# RGBM-05.net
KiCad netlist of a schematic drawn in Altium Designer
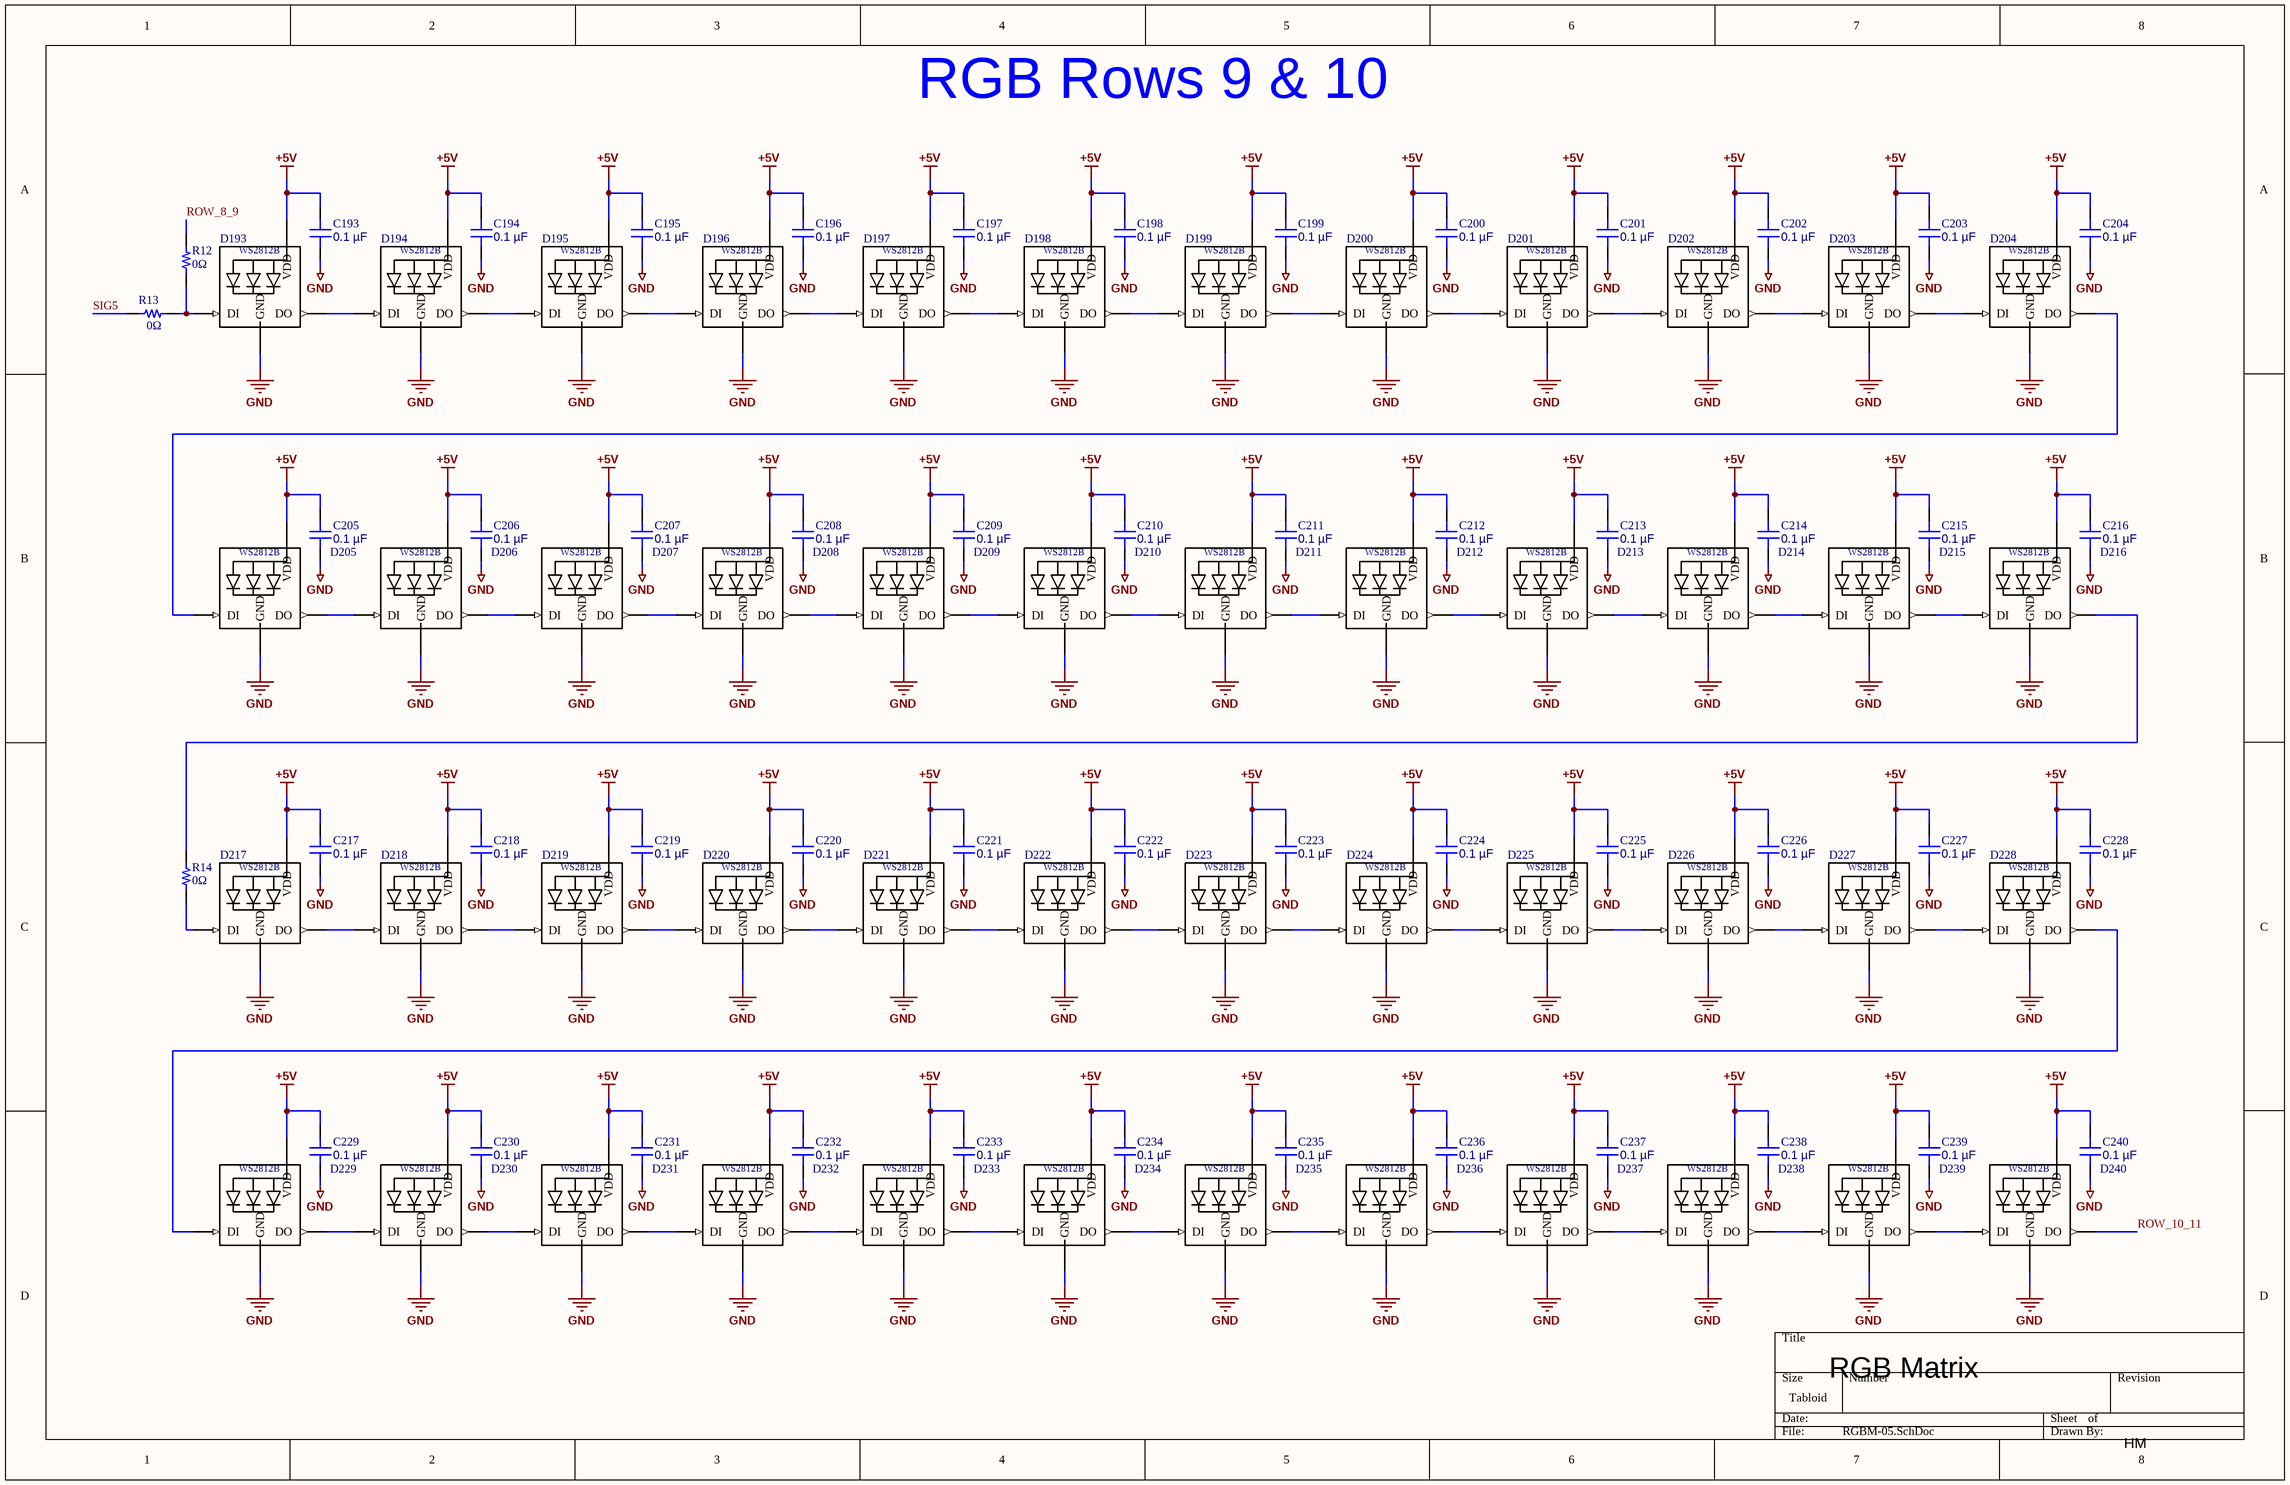
[diagram p0: RGBM-05.SchDoc]

(export (version "E")
  (design (tool "Eeschema 10.0.6"))
  (components
    (comp (ref "C193")
      (value "0.1 µF")
      (footprint "CAP 0603_1608")
      (description "CAP CER 0.1UF 50V X7R 0603")
      (fields
        (field (name "PART NUMBER") "C0603C104K5RAC7411")
        (field (name "CAPACITANCE") "0.1 µF")
        (field (name "MANUFACTURER") "KEMET")
      )
      (libsource (lib "Celestial Altium Library - altium_library") (part "Capacitor"))
    )
    (comp (ref "C194")
      (value "0.1 µF")
      (footprint "CAP 0603_1608")
      (description "CAP CER 0.1UF 50V X7R 0603")
      (fields
        (field (name "PART NUMBER") "C0603C104K5RAC7411")
        (field (name "CAPACITANCE") "0.1 µF")
        (field (name "MANUFACTURER") "KEMET")
      )
      (libsource (lib "Celestial Altium Library - altium_library") (part "Capacitor"))
    )
    (comp (ref "C195")
      (value "0.1 µF")
      (footprint "CAP 0603_1608")
      (description "CAP CER 0.1UF 50V X7R 0603")
      (fields
        (field (name "PART NUMBER") "C0603C104K5RAC7411")
        (field (name "CAPACITANCE") "0.1 µF")
        (field (name "MANUFACTURER") "KEMET")
      )
      (libsource (lib "Celestial Altium Library - altium_library") (part "Capacitor"))
    )
    (comp (ref "C196")
      (value "0.1 µF")
      (footprint "CAP 0603_1608")
      (description "CAP CER 0.1UF 50V X7R 0603")
      (fields
        (field (name "PART NUMBER") "C0603C104K5RAC7411")
        (field (name "CAPACITANCE") "0.1 µF")
        (field (name "MANUFACTURER") "KEMET")
      )
      (libsource (lib "Celestial Altium Library - altium_library") (part "Capacitor"))
    )
    (comp (ref "C197")
      (value "0.1 µF")
      (footprint "CAP 0603_1608")
      (description "CAP CER 0.1UF 50V X7R 0603")
      (fields
        (field (name "PART NUMBER") "C0603C104K5RAC7411")
        (field (name "CAPACITANCE") "0.1 µF")
        (field (name "MANUFACTURER") "KEMET")
      )
      (libsource (lib "Celestial Altium Library - altium_library") (part "Capacitor"))
    )
    (comp (ref "C198")
      (value "0.1 µF")
      (footprint "CAP 0603_1608")
      (description "CAP CER 0.1UF 50V X7R 0603")
      (fields
        (field (name "PART NUMBER") "C0603C104K5RAC7411")
        (field (name "CAPACITANCE") "0.1 µF")
        (field (name "MANUFACTURER") "KEMET")
      )
      (libsource (lib "Celestial Altium Library - altium_library") (part "Capacitor"))
    )
    (comp (ref "C199")
      (value "0.1 µF")
      (footprint "CAP 0603_1608")
      (description "CAP CER 0.1UF 50V X7R 0603")
      (fields
        (field (name "PART NUMBER") "C0603C104K5RAC7411")
        (field (name "CAPACITANCE") "0.1 µF")
        (field (name "MANUFACTURER") "KEMET")
      )
      (libsource (lib "Celestial Altium Library - altium_library") (part "Capacitor"))
    )
    (comp (ref "C200")
      (value "0.1 µF")
      (footprint "CAP 0603_1608")
      (description "CAP CER 0.1UF 50V X7R 0603")
      (fields
        (field (name "PART NUMBER") "C0603C104K5RAC7411")
        (field (name "CAPACITANCE") "0.1 µF")
        (field (name "MANUFACTURER") "KEMET")
      )
      (libsource (lib "Celestial Altium Library - altium_library") (part "Capacitor"))
    )
    (comp (ref "C201")
      (value "0.1 µF")
      (footprint "CAP 0603_1608")
      (description "CAP CER 0.1UF 50V X7R 0603")
      (fields
        (field (name "PART NUMBER") "C0603C104K5RAC7411")
        (field (name "CAPACITANCE") "0.1 µF")
        (field (name "MANUFACTURER") "KEMET")
      )
      (libsource (lib "Celestial Altium Library - altium_library") (part "Capacitor"))
    )
    (comp (ref "C202")
      (value "0.1 µF")
      (footprint "CAP 0603_1608")
      (description "CAP CER 0.1UF 50V X7R 0603")
      (fields
        (field (name "PART NUMBER") "C0603C104K5RAC7411")
        (field (name "CAPACITANCE") "0.1 µF")
        (field (name "MANUFACTURER") "KEMET")
      )
      (libsource (lib "Celestial Altium Library - altium_library") (part "Capacitor"))
    )
    (comp (ref "C203")
      (value "0.1 µF")
      (footprint "CAP 0603_1608")
      (description "CAP CER 0.1UF 50V X7R 0603")
      (fields
        (field (name "PART NUMBER") "C0603C104K5RAC7411")
        (field (name "CAPACITANCE") "0.1 µF")
        (field (name "MANUFACTURER") "KEMET")
      )
      (libsource (lib "Celestial Altium Library - altium_library") (part "Capacitor"))
    )
    (comp (ref "C204")
      (value "0.1 µF")
      (footprint "CAP 0603_1608")
      (description "CAP CER 0.1UF 50V X7R 0603")
      (fields
        (field (name "PART NUMBER") "C0603C104K5RAC7411")
        (field (name "CAPACITANCE") "0.1 µF")
        (field (name "MANUFACTURER") "KEMET")
      )
      (libsource (lib "Celestial Altium Library - altium_library") (part "Capacitor"))
    )
    (comp (ref "C205")
      (value "0.1 µF")
      (footprint "CAP 0603_1608")
      (description "CAP CER 0.1UF 50V X7R 0603")
      (fields
        (field (name "PART NUMBER") "C0603C104K5RAC7411")
        (field (name "CAPACITANCE") "0.1 µF")
        (field (name "MANUFACTURER") "KEMET")
      )
      (libsource (lib "Celestial Altium Library - altium_library") (part "Capacitor"))
    )
    (comp (ref "C206")
      (value "0.1 µF")
      (footprint "CAP 0603_1608")
      (description "CAP CER 0.1UF 50V X7R 0603")
      (fields
        (field (name "PART NUMBER") "C0603C104K5RAC7411")
        (field (name "CAPACITANCE") "0.1 µF")
        (field (name "MANUFACTURER") "KEMET")
      )
      (libsource (lib "Celestial Altium Library - altium_library") (part "Capacitor"))
    )
    (comp (ref "C207")
      (value "0.1 µF")
      (footprint "CAP 0603_1608")
      (description "CAP CER 0.1UF 50V X7R 0603")
      (fields
        (field (name "PART NUMBER") "C0603C104K5RAC7411")
        (field (name "CAPACITANCE") "0.1 µF")
        (field (name "MANUFACTURER") "KEMET")
      )
      (libsource (lib "Celestial Altium Library - altium_library") (part "Capacitor"))
    )
    (comp (ref "C208")
      (value "0.1 µF")
      (footprint "CAP 0603_1608")
      (description "CAP CER 0.1UF 50V X7R 0603")
      (fields
        (field (name "PART NUMBER") "C0603C104K5RAC7411")
        (field (name "CAPACITANCE") "0.1 µF")
        (field (name "MANUFACTURER") "KEMET")
      )
      (libsource (lib "Celestial Altium Library - altium_library") (part "Capacitor"))
    )
    (comp (ref "C209")
      (value "0.1 µF")
      (footprint "CAP 0603_1608")
      (description "CAP CER 0.1UF 50V X7R 0603")
      (fields
        (field (name "PART NUMBER") "C0603C104K5RAC7411")
        (field (name "CAPACITANCE") "0.1 µF")
        (field (name "MANUFACTURER") "KEMET")
      )
      (libsource (lib "Celestial Altium Library - altium_library") (part "Capacitor"))
    )
    (comp (ref "C210")
      (value "0.1 µF")
      (footprint "CAP 0603_1608")
      (description "CAP CER 0.1UF 50V X7R 0603")
      (fields
        (field (name "PART NUMBER") "C0603C104K5RAC7411")
        (field (name "CAPACITANCE") "0.1 µF")
        (field (name "MANUFACTURER") "KEMET")
      )
      (libsource (lib "Celestial Altium Library - altium_library") (part "Capacitor"))
    )
    (comp (ref "C211")
      (value "0.1 µF")
      (footprint "CAP 0603_1608")
      (description "CAP CER 0.1UF 50V X7R 0603")
      (fields
        (field (name "PART NUMBER") "C0603C104K5RAC7411")
        (field (name "CAPACITANCE") "0.1 µF")
        (field (name "MANUFACTURER") "KEMET")
      )
      (libsource (lib "Celestial Altium Library - altium_library") (part "Capacitor"))
    )
    (comp (ref "C212")
      (value "0.1 µF")
      (footprint "CAP 0603_1608")
      (description "CAP CER 0.1UF 50V X7R 0603")
      (fields
        (field (name "PART NUMBER") "C0603C104K5RAC7411")
        (field (name "CAPACITANCE") "0.1 µF")
        (field (name "MANUFACTURER") "KEMET")
      )
      (libsource (lib "Celestial Altium Library - altium_library") (part "Capacitor"))
    )
    (comp (ref "C213")
      (value "0.1 µF")
      (footprint "CAP 0603_1608")
      (description "CAP CER 0.1UF 50V X7R 0603")
      (fields
        (field (name "PART NUMBER") "C0603C104K5RAC7411")
        (field (name "CAPACITANCE") "0.1 µF")
        (field (name "MANUFACTURER") "KEMET")
      )
      (libsource (lib "Celestial Altium Library - altium_library") (part "Capacitor"))
    )
    (comp (ref "C214")
      (value "0.1 µF")
      (footprint "CAP 0603_1608")
      (description "CAP CER 0.1UF 50V X7R 0603")
      (fields
        (field (name "PART NUMBER") "C0603C104K5RAC7411")
        (field (name "CAPACITANCE") "0.1 µF")
        (field (name "MANUFACTURER") "KEMET")
      )
      (libsource (lib "Celestial Altium Library - altium_library") (part "Capacitor"))
    )
    (comp (ref "C215")
      (value "0.1 µF")
      (footprint "CAP 0603_1608")
      (description "CAP CER 0.1UF 50V X7R 0603")
      (fields
        (field (name "PART NUMBER") "C0603C104K5RAC7411")
        (field (name "CAPACITANCE") "0.1 µF")
        (field (name "MANUFACTURER") "KEMET")
      )
      (libsource (lib "Celestial Altium Library - altium_library") (part "Capacitor"))
    )
    (comp (ref "C216")
      (value "0.1 µF")
      (footprint "CAP 0603_1608")
      (description "CAP CER 0.1UF 50V X7R 0603")
      (fields
        (field (name "PART NUMBER") "C0603C104K5RAC7411")
        (field (name "CAPACITANCE") "0.1 µF")
        (field (name "MANUFACTURER") "KEMET")
      )
      (libsource (lib "Celestial Altium Library - altium_library") (part "Capacitor"))
    )
    (comp (ref "C217")
      (value "0.1 µF")
      (footprint "CAP 0603_1608")
      (description "CAP CER 0.1UF 50V X7R 0603")
      (fields
        (field (name "PART NUMBER") "C0603C104K5RAC7411")
        (field (name "CAPACITANCE") "0.1 µF")
        (field (name "MANUFACTURER") "KEMET")
      )
      (libsource (lib "Celestial Altium Library - altium_library") (part "Capacitor"))
    )
    (comp (ref "C218")
      (value "0.1 µF")
      (footprint "CAP 0603_1608")
      (description "CAP CER 0.1UF 50V X7R 0603")
      (fields
        (field (name "PART NUMBER") "C0603C104K5RAC7411")
        (field (name "CAPACITANCE") "0.1 µF")
        (field (name "MANUFACTURER") "KEMET")
      )
      (libsource (lib "Celestial Altium Library - altium_library") (part "Capacitor"))
    )
    (comp (ref "C219")
      (value "0.1 µF")
      (footprint "CAP 0603_1608")
      (description "CAP CER 0.1UF 50V X7R 0603")
      (fields
        (field (name "PART NUMBER") "C0603C104K5RAC7411")
        (field (name "CAPACITANCE") "0.1 µF")
        (field (name "MANUFACTURER") "KEMET")
      )
      (libsource (lib "Celestial Altium Library - altium_library") (part "Capacitor"))
    )
    (comp (ref "C220")
      (value "0.1 µF")
      (footprint "CAP 0603_1608")
      (description "CAP CER 0.1UF 50V X7R 0603")
      (fields
        (field (name "PART NUMBER") "C0603C104K5RAC7411")
        (field (name "CAPACITANCE") "0.1 µF")
        (field (name "MANUFACTURER") "KEMET")
      )
      (libsource (lib "Celestial Altium Library - altium_library") (part "Capacitor"))
    )
    (comp (ref "C221")
      (value "0.1 µF")
      (footprint "CAP 0603_1608")
      (description "CAP CER 0.1UF 50V X7R 0603")
      (fields
        (field (name "PART NUMBER") "C0603C104K5RAC7411")
        (field (name "CAPACITANCE") "0.1 µF")
        (field (name "MANUFACTURER") "KEMET")
      )
      (libsource (lib "Celestial Altium Library - altium_library") (part "Capacitor"))
    )
    (comp (ref "C222")
      (value "0.1 µF")
      (footprint "CAP 0603_1608")
      (description "CAP CER 0.1UF 50V X7R 0603")
      (fields
        (field (name "PART NUMBER") "C0603C104K5RAC7411")
        (field (name "CAPACITANCE") "0.1 µF")
        (field (name "MANUFACTURER") "KEMET")
      )
      (libsource (lib "Celestial Altium Library - altium_library") (part "Capacitor"))
    )
    (comp (ref "C223")
      (value "0.1 µF")
      (footprint "CAP 0603_1608")
      (description "CAP CER 0.1UF 50V X7R 0603")
      (fields
        (field (name "PART NUMBER") "C0603C104K5RAC7411")
        (field (name "CAPACITANCE") "0.1 µF")
        (field (name "MANUFACTURER") "KEMET")
      )
      (libsource (lib "Celestial Altium Library - altium_library") (part "Capacitor"))
    )
    (comp (ref "C224")
      (value "0.1 µF")
      (footprint "CAP 0603_1608")
      (description "CAP CER 0.1UF 50V X7R 0603")
      (fields
        (field (name "PART NUMBER") "C0603C104K5RAC7411")
        (field (name "CAPACITANCE") "0.1 µF")
        (field (name "MANUFACTURER") "KEMET")
      )
      (libsource (lib "Celestial Altium Library - altium_library") (part "Capacitor"))
    )
    (comp (ref "C225")
      (value "0.1 µF")
      (footprint "CAP 0603_1608")
      (description "CAP CER 0.1UF 50V X7R 0603")
      (fields
        (field (name "PART NUMBER") "C0603C104K5RAC7411")
        (field (name "CAPACITANCE") "0.1 µF")
        (field (name "MANUFACTURER") "KEMET")
      )
      (libsource (lib "Celestial Altium Library - altium_library") (part "Capacitor"))
    )
    (comp (ref "C226")
      (value "0.1 µF")
      (footprint "CAP 0603_1608")
      (description "CAP CER 0.1UF 50V X7R 0603")
      (fields
        (field (name "PART NUMBER") "C0603C104K5RAC7411")
        (field (name "CAPACITANCE") "0.1 µF")
        (field (name "MANUFACTURER") "KEMET")
      )
      (libsource (lib "Celestial Altium Library - altium_library") (part "Capacitor"))
    )
    (comp (ref "C227")
      (value "0.1 µF")
      (footprint "CAP 0603_1608")
      (description "CAP CER 0.1UF 50V X7R 0603")
      (fields
        (field (name "PART NUMBER") "C0603C104K5RAC7411")
        (field (name "CAPACITANCE") "0.1 µF")
        (field (name "MANUFACTURER") "KEMET")
      )
      (libsource (lib "Celestial Altium Library - altium_library") (part "Capacitor"))
    )
    (comp (ref "C228")
      (value "0.1 µF")
      (footprint "CAP 0603_1608")
      (description "CAP CER 0.1UF 50V X7R 0603")
      (fields
        (field (name "PART NUMBER") "C0603C104K5RAC7411")
        (field (name "CAPACITANCE") "0.1 µF")
        (field (name "MANUFACTURER") "KEMET")
      )
      (libsource (lib "Celestial Altium Library - altium_library") (part "Capacitor"))
    )
    (comp (ref "C229")
      (value "0.1 µF")
      (footprint "CAP 0603_1608")
      (description "CAP CER 0.1UF 50V X7R 0603")
      (fields
        (field (name "PART NUMBER") "C0603C104K5RAC7411")
        (field (name "CAPACITANCE") "0.1 µF")
        (field (name "MANUFACTURER") "KEMET")
      )
      (libsource (lib "Celestial Altium Library - altium_library") (part "Capacitor"))
    )
    (comp (ref "C230")
      (value "0.1 µF")
      (footprint "CAP 0603_1608")
      (description "CAP CER 0.1UF 50V X7R 0603")
      (fields
        (field (name "PART NUMBER") "C0603C104K5RAC7411")
        (field (name "CAPACITANCE") "0.1 µF")
        (field (name "MANUFACTURER") "KEMET")
      )
      (libsource (lib "Celestial Altium Library - altium_library") (part "Capacitor"))
    )
    (comp (ref "C231")
      (value "0.1 µF")
      (footprint "CAP 0603_1608")
      (description "CAP CER 0.1UF 50V X7R 0603")
      (fields
        (field (name "PART NUMBER") "C0603C104K5RAC7411")
        (field (name "CAPACITANCE") "0.1 µF")
        (field (name "MANUFACTURER") "KEMET")
      )
      (libsource (lib "Celestial Altium Library - altium_library") (part "Capacitor"))
    )
    (comp (ref "C232")
      (value "0.1 µF")
      (footprint "CAP 0603_1608")
      (description "CAP CER 0.1UF 50V X7R 0603")
      (fields
        (field (name "PART NUMBER") "C0603C104K5RAC7411")
        (field (name "CAPACITANCE") "0.1 µF")
        (field (name "MANUFACTURER") "KEMET")
      )
      (libsource (lib "Celestial Altium Library - altium_library") (part "Capacitor"))
    )
    (comp (ref "C233")
      (value "0.1 µF")
      (footprint "CAP 0603_1608")
      (description "CAP CER 0.1UF 50V X7R 0603")
      (fields
        (field (name "PART NUMBER") "C0603C104K5RAC7411")
        (field (name "CAPACITANCE") "0.1 µF")
        (field (name "MANUFACTURER") "KEMET")
      )
      (libsource (lib "Celestial Altium Library - altium_library") (part "Capacitor"))
    )
    (comp (ref "C234")
      (value "0.1 µF")
      (footprint "CAP 0603_1608")
      (description "CAP CER 0.1UF 50V X7R 0603")
      (fields
        (field (name "PART NUMBER") "C0603C104K5RAC7411")
        (field (name "CAPACITANCE") "0.1 µF")
        (field (name "MANUFACTURER") "KEMET")
      )
      (libsource (lib "Celestial Altium Library - altium_library") (part "Capacitor"))
    )
    (comp (ref "C235")
      (value "0.1 µF")
      (footprint "CAP 0603_1608")
      (description "CAP CER 0.1UF 50V X7R 0603")
      (fields
        (field (name "PART NUMBER") "C0603C104K5RAC7411")
        (field (name "CAPACITANCE") "0.1 µF")
        (field (name "MANUFACTURER") "KEMET")
      )
      (libsource (lib "Celestial Altium Library - altium_library") (part "Capacitor"))
    )
    (comp (ref "C236")
      (value "0.1 µF")
      (footprint "CAP 0603_1608")
      (description "CAP CER 0.1UF 50V X7R 0603")
      (fields
        (field (name "PART NUMBER") "C0603C104K5RAC7411")
        (field (name "CAPACITANCE") "0.1 µF")
        (field (name "MANUFACTURER") "KEMET")
      )
      (libsource (lib "Celestial Altium Library - altium_library") (part "Capacitor"))
    )
    (comp (ref "C237")
      (value "0.1 µF")
      (footprint "CAP 0603_1608")
      (description "CAP CER 0.1UF 50V X7R 0603")
      (fields
        (field (name "PART NUMBER") "C0603C104K5RAC7411")
        (field (name "CAPACITANCE") "0.1 µF")
        (field (name "MANUFACTURER") "KEMET")
      )
      (libsource (lib "Celestial Altium Library - altium_library") (part "Capacitor"))
    )
    (comp (ref "C238")
      (value "0.1 µF")
      (footprint "CAP 0603_1608")
      (description "CAP CER 0.1UF 50V X7R 0603")
      (fields
        (field (name "PART NUMBER") "C0603C104K5RAC7411")
        (field (name "CAPACITANCE") "0.1 µF")
        (field (name "MANUFACTURER") "KEMET")
      )
      (libsource (lib "Celestial Altium Library - altium_library") (part "Capacitor"))
    )
    (comp (ref "C239")
      (value "0.1 µF")
      (footprint "CAP 0603_1608")
      (description "CAP CER 0.1UF 50V X7R 0603")
      (fields
        (field (name "PART NUMBER") "C0603C104K5RAC7411")
        (field (name "CAPACITANCE") "0.1 µF")
        (field (name "MANUFACTURER") "KEMET")
      )
      (libsource (lib "Celestial Altium Library - altium_library") (part "Capacitor"))
    )
    (comp (ref "C240")
      (value "0.1 µF")
      (footprint "CAP 0603_1608")
      (description "CAP CER 0.1UF 50V X7R 0603")
      (fields
        (field (name "PART NUMBER") "C0603C104K5RAC7411")
        (field (name "CAPACITANCE") "0.1 µF")
        (field (name "MANUFACTURER") "KEMET")
      )
      (libsource (lib "Celestial Altium Library - altium_library") (part "Capacitor"))
    )
    (comp (ref "D193")
      (value "WS2812B")
      (footprint "*WS2812B_WS2812B(Primary)")
      (description "Intelligent control LED integrated light source")
      (fields (field (name "MF") "Worldsemi"))
      (libsource (lib "WS2812B") (part "WS2812B"))
    )
    (comp (ref "D194")
      (value "WS2812B")
      (footprint "*WS2812B_WS2812B(Primary)")
      (description "Intelligent control LED integrated light source")
      (fields (field (name "MF") "Worldsemi"))
      (libsource (lib "WS2812B") (part "WS2812B"))
    )
    (comp (ref "D195")
      (value "WS2812B")
      (footprint "*WS2812B_WS2812B(Primary)")
      (description "Intelligent control LED integrated light source")
      (fields (field (name "MF") "Worldsemi"))
      (libsource (lib "WS2812B") (part "WS2812B"))
    )
    (comp (ref "D196")
      (value "WS2812B")
      (footprint "*WS2812B_WS2812B(Primary)")
      (description "Intelligent control LED integrated light source")
      (fields (field (name "MF") "Worldsemi"))
      (libsource (lib "WS2812B") (part "WS2812B"))
    )
    (comp (ref "D197")
      (value "WS2812B")
      (footprint "*WS2812B_WS2812B(Primary)")
      (description "Intelligent control LED integrated light source")
      (fields (field (name "MF") "Worldsemi"))
      (libsource (lib "WS2812B") (part "WS2812B"))
    )
    (comp (ref "D198")
      (value "WS2812B")
      (footprint "*WS2812B_WS2812B(Primary)")
      (description "Intelligent control LED integrated light source")
      (fields (field (name "MF") "Worldsemi"))
      (libsource (lib "WS2812B") (part "WS2812B"))
    )
    (comp (ref "D199")
      (value "WS2812B")
      (footprint "*WS2812B_WS2812B(Primary)")
      (description "Intelligent control LED integrated light source")
      (fields (field (name "MF") "Worldsemi"))
      (libsource (lib "WS2812B") (part "WS2812B"))
    )
    (comp (ref "D200")
      (value "WS2812B")
      (footprint "*WS2812B_WS2812B(Primary)")
      (description "Intelligent control LED integrated light source")
      (fields (field (name "MF") "Worldsemi"))
      (libsource (lib "WS2812B") (part "WS2812B"))
    )
    (comp (ref "D201")
      (value "WS2812B")
      (footprint "*WS2812B_WS2812B(Primary)")
      (description "Intelligent control LED integrated light source")
      (fields (field (name "MF") "Worldsemi"))
      (libsource (lib "WS2812B") (part "WS2812B"))
    )
    (comp (ref "D202")
      (value "WS2812B")
      (footprint "*WS2812B_WS2812B(Primary)")
      (description "Intelligent control LED integrated light source")
      (fields (field (name "MF") "Worldsemi"))
      (libsource (lib "WS2812B") (part "WS2812B"))
    )
    (comp (ref "D203")
      (value "WS2812B")
      (footprint "*WS2812B_WS2812B(Primary)")
      (description "Intelligent control LED integrated light source")
      (fields (field (name "MF") "Worldsemi"))
      (libsource (lib "WS2812B") (part "WS2812B"))
    )
    (comp (ref "D204")
      (value "WS2812B")
      (footprint "*WS2812B_WS2812B(Primary)")
      (description "Intelligent control LED integrated light source")
      (fields (field (name "MF") "Worldsemi"))
      (libsource (lib "WS2812B") (part "WS2812B"))
    )
    (comp (ref "D205")
      (value "WS2812B")
      (footprint "*WS2812B_WS2812B(Primary)")
      (description "Intelligent control LED integrated light source")
      (fields (field (name "MF") "Worldsemi"))
      (libsource (lib "WS2812B") (part "WS2812B"))
    )
    (comp (ref "D206")
      (value "WS2812B")
      (footprint "*WS2812B_WS2812B(Primary)")
      (description "Intelligent control LED integrated light source")
      (fields (field (name "MF") "Worldsemi"))
      (libsource (lib "WS2812B") (part "WS2812B"))
    )
    (comp (ref "D207")
      (value "WS2812B")
      (footprint "*WS2812B_WS2812B(Primary)")
      (description "Intelligent control LED integrated light source")
      (fields (field (name "MF") "Worldsemi"))
      (libsource (lib "WS2812B") (part "WS2812B"))
    )
    (comp (ref "D208")
      (value "WS2812B")
      (footprint "*WS2812B_WS2812B(Primary)")
      (description "Intelligent control LED integrated light source")
      (fields (field (name "MF") "Worldsemi"))
      (libsource (lib "WS2812B") (part "WS2812B"))
    )
    (comp (ref "D209")
      (value "WS2812B")
      (footprint "*WS2812B_WS2812B(Primary)")
      (description "Intelligent control LED integrated light source")
      (fields (field (name "MF") "Worldsemi"))
      (libsource (lib "WS2812B") (part "WS2812B"))
    )
    (comp (ref "D210")
      (value "WS2812B")
      (footprint "*WS2812B_WS2812B(Primary)")
      (description "Intelligent control LED integrated light source")
      (fields (field (name "MF") "Worldsemi"))
      (libsource (lib "WS2812B") (part "WS2812B"))
    )
    (comp (ref "D211")
      (value "WS2812B")
      (footprint "*WS2812B_WS2812B(Primary)")
      (description "Intelligent control LED integrated light source")
      (fields (field (name "MF") "Worldsemi"))
      (libsource (lib "WS2812B") (part "WS2812B"))
    )
    (comp (ref "D212")
      (value "WS2812B")
      (footprint "*WS2812B_WS2812B(Primary)")
      (description "Intelligent control LED integrated light source")
      (fields (field (name "MF") "Worldsemi"))
      (libsource (lib "WS2812B") (part "WS2812B"))
    )
    (comp (ref "D213")
      (value "WS2812B")
      (footprint "*WS2812B_WS2812B(Primary)")
      (description "Intelligent control LED integrated light source")
      (fields (field (name "MF") "Worldsemi"))
      (libsource (lib "WS2812B") (part "WS2812B"))
    )
    (comp (ref "D214")
      (value "WS2812B")
      (footprint "*WS2812B_WS2812B(Primary)")
      (description "Intelligent control LED integrated light source")
      (fields (field (name "MF") "Worldsemi"))
      (libsource (lib "WS2812B") (part "WS2812B"))
    )
    (comp (ref "D215")
      (value "WS2812B")
      (footprint "*WS2812B_WS2812B(Primary)")
      (description "Intelligent control LED integrated light source")
      (fields (field (name "MF") "Worldsemi"))
      (libsource (lib "WS2812B") (part "WS2812B"))
    )
    (comp (ref "D216")
      (value "WS2812B")
      (footprint "*WS2812B_WS2812B(Primary)")
      (description "Intelligent control LED integrated light source")
      (fields (field (name "MF") "Worldsemi"))
      (libsource (lib "WS2812B") (part "WS2812B"))
    )
    (comp (ref "D217")
      (value "WS2812B")
      (footprint "*WS2812B_WS2812B(Primary)")
      (description "Intelligent control LED integrated light source")
      (fields (field (name "MF") "Worldsemi"))
      (libsource (lib "WS2812B") (part "WS2812B"))
    )
    (comp (ref "D218")
      (value "WS2812B")
      (footprint "*WS2812B_WS2812B(Primary)")
      (description "Intelligent control LED integrated light source")
      (fields (field (name "MF") "Worldsemi"))
      (libsource (lib "WS2812B") (part "WS2812B"))
    )
    (comp (ref "D219")
      (value "WS2812B")
      (footprint "*WS2812B_WS2812B(Primary)")
      (description "Intelligent control LED integrated light source")
      (fields (field (name "MF") "Worldsemi"))
      (libsource (lib "WS2812B") (part "WS2812B"))
    )
    (comp (ref "D220")
      (value "WS2812B")
      (footprint "*WS2812B_WS2812B(Primary)")
      (description "Intelligent control LED integrated light source")
      (fields (field (name "MF") "Worldsemi"))
      (libsource (lib "WS2812B") (part "WS2812B"))
    )
    (comp (ref "D221")
      (value "WS2812B")
      (footprint "*WS2812B_WS2812B(Primary)")
      (description "Intelligent control LED integrated light source")
      (fields (field (name "MF") "Worldsemi"))
      (libsource (lib "WS2812B") (part "WS2812B"))
    )
    (comp (ref "D222")
      (value "WS2812B")
      (footprint "*WS2812B_WS2812B(Primary)")
      (description "Intelligent control LED integrated light source")
      (fields (field (name "MF") "Worldsemi"))
      (libsource (lib "WS2812B") (part "WS2812B"))
    )
    (comp (ref "D223")
      (value "WS2812B")
      (footprint "*WS2812B_WS2812B(Primary)")
      (description "Intelligent control LED integrated light source")
      (fields (field (name "MF") "Worldsemi"))
      (libsource (lib "WS2812B") (part "WS2812B"))
    )
    (comp (ref "D224")
      (value "WS2812B")
      (footprint "*WS2812B_WS2812B(Primary)")
      (description "Intelligent control LED integrated light source")
      (fields (field (name "MF") "Worldsemi"))
      (libsource (lib "WS2812B") (part "WS2812B"))
    )
    (comp (ref "D225")
      (value "WS2812B")
      (footprint "*WS2812B_WS2812B(Primary)")
      (description "Intelligent control LED integrated light source")
      (fields (field (name "MF") "Worldsemi"))
      (libsource (lib "WS2812B") (part "WS2812B"))
    )
    (comp (ref "D226")
      (value "WS2812B")
      (footprint "*WS2812B_WS2812B(Primary)")
      (description "Intelligent control LED integrated light source")
      (fields (field (name "MF") "Worldsemi"))
      (libsource (lib "WS2812B") (part "WS2812B"))
    )
    (comp (ref "D227")
      (value "WS2812B")
      (footprint "*WS2812B_WS2812B(Primary)")
      (description "Intelligent control LED integrated light source")
      (fields (field (name "MF") "Worldsemi"))
      (libsource (lib "WS2812B") (part "WS2812B"))
    )
    (comp (ref "D228")
      (value "WS2812B")
      (footprint "*WS2812B_WS2812B(Primary)")
      (description "Intelligent control LED integrated light source")
      (fields (field (name "MF") "Worldsemi"))
      (libsource (lib "WS2812B") (part "WS2812B"))
    )
    (comp (ref "D229")
      (value "WS2812B")
      (footprint "*WS2812B_WS2812B(Primary)")
      (description "Intelligent control LED integrated light source")
      (fields (field (name "MF") "Worldsemi"))
      (libsource (lib "WS2812B") (part "WS2812B"))
    )
    (comp (ref "D230")
      (value "WS2812B")
      (footprint "*WS2812B_WS2812B(Primary)")
      (description "Intelligent control LED integrated light source")
      (fields (field (name "MF") "Worldsemi"))
      (libsource (lib "WS2812B") (part "WS2812B"))
    )
    (comp (ref "D231")
      (value "WS2812B")
      (footprint "*WS2812B_WS2812B(Primary)")
      (description "Intelligent control LED integrated light source")
      (fields (field (name "MF") "Worldsemi"))
      (libsource (lib "WS2812B") (part "WS2812B"))
    )
    (comp (ref "D232")
      (value "WS2812B")
      (footprint "*WS2812B_WS2812B(Primary)")
      (description "Intelligent control LED integrated light source")
      (fields (field (name "MF") "Worldsemi"))
      (libsource (lib "WS2812B") (part "WS2812B"))
    )
    (comp (ref "D233")
      (value "WS2812B")
      (footprint "*WS2812B_WS2812B(Primary)")
      (description "Intelligent control LED integrated light source")
      (fields (field (name "MF") "Worldsemi"))
      (libsource (lib "WS2812B") (part "WS2812B"))
    )
    (comp (ref "D234")
      (value "WS2812B")
      (footprint "*WS2812B_WS2812B(Primary)")
      (description "Intelligent control LED integrated light source")
      (fields (field (name "MF") "Worldsemi"))
      (libsource (lib "WS2812B") (part "WS2812B"))
    )
    (comp (ref "D235")
      (value "WS2812B")
      (footprint "*WS2812B_WS2812B(Primary)")
      (description "Intelligent control LED integrated light source")
      (fields (field (name "MF") "Worldsemi"))
      (libsource (lib "WS2812B") (part "WS2812B"))
    )
    (comp (ref "D236")
      (value "WS2812B")
      (footprint "*WS2812B_WS2812B(Primary)")
      (description "Intelligent control LED integrated light source")
      (fields (field (name "MF") "Worldsemi"))
      (libsource (lib "WS2812B") (part "WS2812B"))
    )
    (comp (ref "D237")
      (value "WS2812B")
      (footprint "*WS2812B_WS2812B(Primary)")
      (description "Intelligent control LED integrated light source")
      (fields (field (name "MF") "Worldsemi"))
      (libsource (lib "WS2812B") (part "WS2812B"))
    )
    (comp (ref "D238")
      (value "WS2812B")
      (footprint "*WS2812B_WS2812B(Primary)")
      (description "Intelligent control LED integrated light source")
      (fields (field (name "MF") "Worldsemi"))
      (libsource (lib "WS2812B") (part "WS2812B"))
    )
    (comp (ref "D239")
      (value "WS2812B")
      (footprint "*WS2812B_WS2812B(Primary)")
      (description "Intelligent control LED integrated light source")
      (fields (field (name "MF") "Worldsemi"))
      (libsource (lib "WS2812B") (part "WS2812B"))
    )
    (comp (ref "D240")
      (value "WS2812B")
      (footprint "*WS2812B_WS2812B(Primary)")
      (description "Intelligent control LED integrated light source")
      (fields (field (name "MF") "Worldsemi"))
      (libsource (lib "WS2812B") (part "WS2812B"))
    )
    (comp (ref "R12")
      (value "0Ω")
      (footprint "RES 0603_1608")
      (description "RES SMD 0 OHM JUMPER 0603")
      (fields (field (name "PART NUMBER") "YJP1608-R001") (field (name "MANUFACTURER") "Susumu"))
      (libsource (lib "Celestial Altium Library - altium_library") (part "Resistor"))
    )
    (comp (ref "R13")
      (value "0Ω")
      (footprint "RES 0603_1608")
      (description "RES SMD 0 OHM JUMPER 0603")
      (fields (field (name "PART NUMBER") "YJP1608-R001") (field (name "MANUFACTURER") "Susumu"))
      (libsource (lib "Celestial Altium Library - altium_library") (part "Resistor"))
    )
    (comp (ref "R14")
      (value "0Ω")
      (footprint "RES 0603_1608")
      (description "RES SMD 0 OHM JUMPER 0603")
      (fields (field (name "PART NUMBER") "YJP1608-R001") (field (name "MANUFACTURER") "Susumu"))
      (libsource (lib "Celestial Altium Library - altium_library") (part "Resistor"))
    )
  )
  (nets
    (net (code "1") (name "+5V") (class "Default")
      (node (ref "C193") (pin "2") (pinfunction "2_2") (pintype "passive"))
      (node (ref "C194") (pin "2") (pinfunction "2_2") (pintype "passive"))
      (node (ref "C195") (pin "2") (pinfunction "2_2") (pintype "passive"))
      (node (ref "C196") (pin "2") (pinfunction "2_2") (pintype "passive"))
      (node (ref "C197") (pin "2") (pinfunction "2_2") (pintype "passive"))
      (node (ref "C198") (pin "2") (pinfunction "2_2") (pintype "passive"))
      (node (ref "C199") (pin "2") (pinfunction "2_2") (pintype "passive"))
      (node (ref "C200") (pin "2") (pinfunction "2_2") (pintype "passive"))
      (node (ref "C201") (pin "2") (pinfunction "2_2") (pintype "passive"))
      (node (ref "C202") (pin "2") (pinfunction "2_2") (pintype "passive"))
      (node (ref "C203") (pin "2") (pinfunction "2_2") (pintype "passive"))
      (node (ref "C204") (pin "2") (pinfunction "2_2") (pintype "passive"))
      (node (ref "C205") (pin "2") (pinfunction "2_2") (pintype "passive"))
      (node (ref "C206") (pin "2") (pinfunction "2_2") (pintype "passive"))
      (node (ref "C207") (pin "2") (pinfunction "2_2") (pintype "passive"))
      (node (ref "C208") (pin "2") (pinfunction "2_2") (pintype "passive"))
      (node (ref "C209") (pin "2") (pinfunction "2_2") (pintype "passive"))
      (node (ref "C210") (pin "2") (pinfunction "2_2") (pintype "passive"))
      (node (ref "C211") (pin "2") (pinfunction "2_2") (pintype "passive"))
      (node (ref "C212") (pin "2") (pinfunction "2_2") (pintype "passive"))
      (node (ref "C213") (pin "2") (pinfunction "2_2") (pintype "passive"))
      (node (ref "C214") (pin "2") (pinfunction "2_2") (pintype "passive"))
      (node (ref "C215") (pin "2") (pinfunction "2_2") (pintype "passive"))
      (node (ref "C216") (pin "2") (pinfunction "2_2") (pintype "passive"))
      (node (ref "C217") (pin "2") (pinfunction "2_2") (pintype "passive"))
      (node (ref "C218") (pin "2") (pinfunction "2_2") (pintype "passive"))
      (node (ref "C219") (pin "2") (pinfunction "2_2") (pintype "passive"))
      (node (ref "C220") (pin "2") (pinfunction "2_2") (pintype "passive"))
      (node (ref "C221") (pin "2") (pinfunction "2_2") (pintype "passive"))
      (node (ref "C222") (pin "2") (pinfunction "2_2") (pintype "passive"))
      (node (ref "C223") (pin "2") (pinfunction "2_2") (pintype "passive"))
      (node (ref "C224") (pin "2") (pinfunction "2_2") (pintype "passive"))
      (node (ref "C225") (pin "2") (pinfunction "2_2") (pintype "passive"))
      (node (ref "C226") (pin "2") (pinfunction "2_2") (pintype "passive"))
      (node (ref "C227") (pin "2") (pinfunction "2_2") (pintype "passive"))
      (node (ref "C228") (pin "2") (pinfunction "2_2") (pintype "passive"))
      (node (ref "C229") (pin "2") (pinfunction "2_2") (pintype "passive"))
      (node (ref "C230") (pin "2") (pinfunction "2_2") (pintype "passive"))
      (node (ref "C231") (pin "2") (pinfunction "2_2") (pintype "passive"))
      (node (ref "C232") (pin "2") (pinfunction "2_2") (pintype "passive"))
      (node (ref "C233") (pin "2") (pinfunction "2_2") (pintype "passive"))
      (node (ref "C234") (pin "2") (pinfunction "2_2") (pintype "passive"))
      (node (ref "C235") (pin "2") (pinfunction "2_2") (pintype "passive"))
      (node (ref "C236") (pin "2") (pinfunction "2_2") (pintype "passive"))
      (node (ref "C237") (pin "2") (pinfunction "2_2") (pintype "passive"))
      (node (ref "C238") (pin "2") (pinfunction "2_2") (pintype "passive"))
      (node (ref "C239") (pin "2") (pinfunction "2_2") (pintype "passive"))
      (node (ref "C240") (pin "2") (pinfunction "2_2") (pintype "passive"))
      (node (ref "D193") (pin "1-VDD") (pinfunction "VDD_1-VDD") (pintype "power_in"))
      (node (ref "D194") (pin "1-VDD") (pinfunction "VDD_1-VDD") (pintype "power_in"))
      (node (ref "D195") (pin "1-VDD") (pinfunction "VDD_1-VDD") (pintype "power_in"))
      (node (ref "D196") (pin "1-VDD") (pinfunction "VDD_1-VDD") (pintype "power_in"))
      (node (ref "D197") (pin "1-VDD") (pinfunction "VDD_1-VDD") (pintype "power_in"))
      (node (ref "D198") (pin "1-VDD") (pinfunction "VDD_1-VDD") (pintype "power_in"))
      (node (ref "D199") (pin "1-VDD") (pinfunction "VDD_1-VDD") (pintype "power_in"))
      (node (ref "D200") (pin "1-VDD") (pinfunction "VDD_1-VDD") (pintype "power_in"))
      (node (ref "D201") (pin "1-VDD") (pinfunction "VDD_1-VDD") (pintype "power_in"))
      (node (ref "D202") (pin "1-VDD") (pinfunction "VDD_1-VDD") (pintype "power_in"))
      (node (ref "D203") (pin "1-VDD") (pinfunction "VDD_1-VDD") (pintype "power_in"))
      (node (ref "D204") (pin "1-VDD") (pinfunction "VDD_1-VDD") (pintype "power_in"))
      (node (ref "D205") (pin "1-VDD") (pinfunction "VDD_1-VDD") (pintype "power_in"))
      (node (ref "D206") (pin "1-VDD") (pinfunction "VDD_1-VDD") (pintype "power_in"))
      (node (ref "D207") (pin "1-VDD") (pinfunction "VDD_1-VDD") (pintype "power_in"))
      (node (ref "D208") (pin "1-VDD") (pinfunction "VDD_1-VDD") (pintype "power_in"))
      (node (ref "D209") (pin "1-VDD") (pinfunction "VDD_1-VDD") (pintype "power_in"))
      (node (ref "D210") (pin "1-VDD") (pinfunction "VDD_1-VDD") (pintype "power_in"))
      (node (ref "D211") (pin "1-VDD") (pinfunction "VDD_1-VDD") (pintype "power_in"))
      (node (ref "D212") (pin "1-VDD") (pinfunction "VDD_1-VDD") (pintype "power_in"))
      (node (ref "D213") (pin "1-VDD") (pinfunction "VDD_1-VDD") (pintype "power_in"))
      (node (ref "D214") (pin "1-VDD") (pinfunction "VDD_1-VDD") (pintype "power_in"))
      (node (ref "D215") (pin "1-VDD") (pinfunction "VDD_1-VDD") (pintype "power_in"))
      (node (ref "D216") (pin "1-VDD") (pinfunction "VDD_1-VDD") (pintype "power_in"))
      (node (ref "D217") (pin "1-VDD") (pinfunction "VDD_1-VDD") (pintype "power_in"))
      (node (ref "D218") (pin "1-VDD") (pinfunction "VDD_1-VDD") (pintype "power_in"))
      (node (ref "D219") (pin "1-VDD") (pinfunction "VDD_1-VDD") (pintype "power_in"))
      (node (ref "D220") (pin "1-VDD") (pinfunction "VDD_1-VDD") (pintype "power_in"))
      (node (ref "D221") (pin "1-VDD") (pinfunction "VDD_1-VDD") (pintype "power_in"))
      (node (ref "D222") (pin "1-VDD") (pinfunction "VDD_1-VDD") (pintype "power_in"))
      (node (ref "D223") (pin "1-VDD") (pinfunction "VDD_1-VDD") (pintype "power_in"))
      (node (ref "D224") (pin "1-VDD") (pinfunction "VDD_1-VDD") (pintype "power_in"))
      (node (ref "D225") (pin "1-VDD") (pinfunction "VDD_1-VDD") (pintype "power_in"))
      (node (ref "D226") (pin "1-VDD") (pinfunction "VDD_1-VDD") (pintype "power_in"))
      (node (ref "D227") (pin "1-VDD") (pinfunction "VDD_1-VDD") (pintype "power_in"))
      (node (ref "D228") (pin "1-VDD") (pinfunction "VDD_1-VDD") (pintype "power_in"))
      (node (ref "D229") (pin "1-VDD") (pinfunction "VDD_1-VDD") (pintype "power_in"))
      (node (ref "D230") (pin "1-VDD") (pinfunction "VDD_1-VDD") (pintype "power_in"))
      (node (ref "D231") (pin "1-VDD") (pinfunction "VDD_1-VDD") (pintype "power_in"))
      (node (ref "D232") (pin "1-VDD") (pinfunction "VDD_1-VDD") (pintype "power_in"))
      (node (ref "D233") (pin "1-VDD") (pinfunction "VDD_1-VDD") (pintype "power_in"))
      (node (ref "D234") (pin "1-VDD") (pinfunction "VDD_1-VDD") (pintype "power_in"))
      (node (ref "D235") (pin "1-VDD") (pinfunction "VDD_1-VDD") (pintype "power_in"))
      (node (ref "D236") (pin "1-VDD") (pinfunction "VDD_1-VDD") (pintype "power_in"))
      (node (ref "D237") (pin "1-VDD") (pinfunction "VDD_1-VDD") (pintype "power_in"))
      (node (ref "D238") (pin "1-VDD") (pinfunction "VDD_1-VDD") (pintype "power_in"))
      (node (ref "D239") (pin "1-VDD") (pinfunction "VDD_1-VDD") (pintype "power_in"))
      (node (ref "D240") (pin "1-VDD") (pinfunction "VDD_1-VDD") (pintype "power_in"))
    )
    (net (code "2") (name "/ROW_8_9") (class "Default")
      (node (ref "R12") (pin "2") (pinfunction "2_2") (pintype "passive"))
    )
    (net (code "3") (name "/ROW_10_11") (class "Default")
      (node (ref "D240") (pin "2-DOUT") (pinfunction "DO_2-DOUT") (pintype "output"))
    )
    (net (code "4") (name "/SIG5") (class "Default")
      (node (ref "R13") (pin "1") (pinfunction "1_1") (pintype "passive"))
    )
    (net (code "5") (name "GND") (class "Default")
      (node (ref "C193") (pin "1") (pinfunction "1_1") (pintype "passive"))
      (node (ref "C194") (pin "1") (pinfunction "1_1") (pintype "passive"))
      (node (ref "C195") (pin "1") (pinfunction "1_1") (pintype "passive"))
      (node (ref "C196") (pin "1") (pinfunction "1_1") (pintype "passive"))
      (node (ref "C197") (pin "1") (pinfunction "1_1") (pintype "passive"))
      (node (ref "C198") (pin "1") (pinfunction "1_1") (pintype "passive"))
      (node (ref "C199") (pin "1") (pinfunction "1_1") (pintype "passive"))
      (node (ref "C200") (pin "1") (pinfunction "1_1") (pintype "passive"))
      (node (ref "C201") (pin "1") (pinfunction "1_1") (pintype "passive"))
      (node (ref "C202") (pin "1") (pinfunction "1_1") (pintype "passive"))
      (node (ref "C203") (pin "1") (pinfunction "1_1") (pintype "passive"))
      (node (ref "C204") (pin "1") (pinfunction "1_1") (pintype "passive"))
      (node (ref "C205") (pin "1") (pinfunction "1_1") (pintype "passive"))
      (node (ref "C206") (pin "1") (pinfunction "1_1") (pintype "passive"))
      (node (ref "C207") (pin "1") (pinfunction "1_1") (pintype "passive"))
      (node (ref "C208") (pin "1") (pinfunction "1_1") (pintype "passive"))
      (node (ref "C209") (pin "1") (pinfunction "1_1") (pintype "passive"))
      (node (ref "C210") (pin "1") (pinfunction "1_1") (pintype "passive"))
      (node (ref "C211") (pin "1") (pinfunction "1_1") (pintype "passive"))
      (node (ref "C212") (pin "1") (pinfunction "1_1") (pintype "passive"))
      (node (ref "C213") (pin "1") (pinfunction "1_1") (pintype "passive"))
      (node (ref "C214") (pin "1") (pinfunction "1_1") (pintype "passive"))
      (node (ref "C215") (pin "1") (pinfunction "1_1") (pintype "passive"))
      (node (ref "C216") (pin "1") (pinfunction "1_1") (pintype "passive"))
      (node (ref "C217") (pin "1") (pinfunction "1_1") (pintype "passive"))
      (node (ref "C218") (pin "1") (pinfunction "1_1") (pintype "passive"))
      (node (ref "C219") (pin "1") (pinfunction "1_1") (pintype "passive"))
      (node (ref "C220") (pin "1") (pinfunction "1_1") (pintype "passive"))
      (node (ref "C221") (pin "1") (pinfunction "1_1") (pintype "passive"))
      (node (ref "C222") (pin "1") (pinfunction "1_1") (pintype "passive"))
      (node (ref "C223") (pin "1") (pinfunction "1_1") (pintype "passive"))
      (node (ref "C224") (pin "1") (pinfunction "1_1") (pintype "passive"))
      (node (ref "C225") (pin "1") (pinfunction "1_1") (pintype "passive"))
      (node (ref "C226") (pin "1") (pinfunction "1_1") (pintype "passive"))
      (node (ref "C227") (pin "1") (pinfunction "1_1") (pintype "passive"))
      (node (ref "C228") (pin "1") (pinfunction "1_1") (pintype "passive"))
      (node (ref "C229") (pin "1") (pinfunction "1_1") (pintype "passive"))
      (node (ref "C230") (pin "1") (pinfunction "1_1") (pintype "passive"))
      (node (ref "C231") (pin "1") (pinfunction "1_1") (pintype "passive"))
      (node (ref "C232") (pin "1") (pinfunction "1_1") (pintype "passive"))
      (node (ref "C233") (pin "1") (pinfunction "1_1") (pintype "passive"))
      (node (ref "C234") (pin "1") (pinfunction "1_1") (pintype "passive"))
      (node (ref "C235") (pin "1") (pinfunction "1_1") (pintype "passive"))
      (node (ref "C236") (pin "1") (pinfunction "1_1") (pintype "passive"))
      (node (ref "C237") (pin "1") (pinfunction "1_1") (pintype "passive"))
      (node (ref "C238") (pin "1") (pinfunction "1_1") (pintype "passive"))
      (node (ref "C239") (pin "1") (pinfunction "1_1") (pintype "passive"))
      (node (ref "C240") (pin "1") (pinfunction "1_1") (pintype "passive"))
      (node (ref "D193") (pin "3-GND") (pinfunction "GND_3-GND") (pintype "power_in"))
      (node (ref "D194") (pin "3-GND") (pinfunction "GND_3-GND") (pintype "power_in"))
      (node (ref "D195") (pin "3-GND") (pinfunction "GND_3-GND") (pintype "power_in"))
      (node (ref "D196") (pin "3-GND") (pinfunction "GND_3-GND") (pintype "power_in"))
      (node (ref "D197") (pin "3-GND") (pinfunction "GND_3-GND") (pintype "power_in"))
      (node (ref "D198") (pin "3-GND") (pinfunction "GND_3-GND") (pintype "power_in"))
      (node (ref "D199") (pin "3-GND") (pinfunction "GND_3-GND") (pintype "power_in"))
      (node (ref "D200") (pin "3-GND") (pinfunction "GND_3-GND") (pintype "power_in"))
      (node (ref "D201") (pin "3-GND") (pinfunction "GND_3-GND") (pintype "power_in"))
      (node (ref "D202") (pin "3-GND") (pinfunction "GND_3-GND") (pintype "power_in"))
      (node (ref "D203") (pin "3-GND") (pinfunction "GND_3-GND") (pintype "power_in"))
      (node (ref "D204") (pin "3-GND") (pinfunction "GND_3-GND") (pintype "power_in"))
      (node (ref "D205") (pin "3-GND") (pinfunction "GND_3-GND") (pintype "power_in"))
      (node (ref "D206") (pin "3-GND") (pinfunction "GND_3-GND") (pintype "power_in"))
      (node (ref "D207") (pin "3-GND") (pinfunction "GND_3-GND") (pintype "power_in"))
      (node (ref "D208") (pin "3-GND") (pinfunction "GND_3-GND") (pintype "power_in"))
      (node (ref "D209") (pin "3-GND") (pinfunction "GND_3-GND") (pintype "power_in"))
      (node (ref "D210") (pin "3-GND") (pinfunction "GND_3-GND") (pintype "power_in"))
      (node (ref "D211") (pin "3-GND") (pinfunction "GND_3-GND") (pintype "power_in"))
      (node (ref "D212") (pin "3-GND") (pinfunction "GND_3-GND") (pintype "power_in"))
      (node (ref "D213") (pin "3-GND") (pinfunction "GND_3-GND") (pintype "power_in"))
      (node (ref "D214") (pin "3-GND") (pinfunction "GND_3-GND") (pintype "power_in"))
      (node (ref "D215") (pin "3-GND") (pinfunction "GND_3-GND") (pintype "power_in"))
      (node (ref "D216") (pin "3-GND") (pinfunction "GND_3-GND") (pintype "power_in"))
      (node (ref "D217") (pin "3-GND") (pinfunction "GND_3-GND") (pintype "power_in"))
      (node (ref "D218") (pin "3-GND") (pinfunction "GND_3-GND") (pintype "power_in"))
      (node (ref "D219") (pin "3-GND") (pinfunction "GND_3-GND") (pintype "power_in"))
      (node (ref "D220") (pin "3-GND") (pinfunction "GND_3-GND") (pintype "power_in"))
      (node (ref "D221") (pin "3-GND") (pinfunction "GND_3-GND") (pintype "power_in"))
      (node (ref "D222") (pin "3-GND") (pinfunction "GND_3-GND") (pintype "power_in"))
      (node (ref "D223") (pin "3-GND") (pinfunction "GND_3-GND") (pintype "power_in"))
      (node (ref "D224") (pin "3-GND") (pinfunction "GND_3-GND") (pintype "power_in"))
      (node (ref "D225") (pin "3-GND") (pinfunction "GND_3-GND") (pintype "power_in"))
      (node (ref "D226") (pin "3-GND") (pinfunction "GND_3-GND") (pintype "power_in"))
      (node (ref "D227") (pin "3-GND") (pinfunction "GND_3-GND") (pintype "power_in"))
      (node (ref "D228") (pin "3-GND") (pinfunction "GND_3-GND") (pintype "power_in"))
      (node (ref "D229") (pin "3-GND") (pinfunction "GND_3-GND") (pintype "power_in"))
      (node (ref "D230") (pin "3-GND") (pinfunction "GND_3-GND") (pintype "power_in"))
      (node (ref "D231") (pin "3-GND") (pinfunction "GND_3-GND") (pintype "power_in"))
      (node (ref "D232") (pin "3-GND") (pinfunction "GND_3-GND") (pintype "power_in"))
      (node (ref "D233") (pin "3-GND") (pinfunction "GND_3-GND") (pintype "power_in"))
      (node (ref "D234") (pin "3-GND") (pinfunction "GND_3-GND") (pintype "power_in"))
      (node (ref "D235") (pin "3-GND") (pinfunction "GND_3-GND") (pintype "power_in"))
      (node (ref "D236") (pin "3-GND") (pinfunction "GND_3-GND") (pintype "power_in"))
      (node (ref "D237") (pin "3-GND") (pinfunction "GND_3-GND") (pintype "power_in"))
      (node (ref "D238") (pin "3-GND") (pinfunction "GND_3-GND") (pintype "power_in"))
      (node (ref "D239") (pin "3-GND") (pinfunction "GND_3-GND") (pintype "power_in"))
      (node (ref "D240") (pin "3-GND") (pinfunction "GND_3-GND") (pintype "power_in"))
    )
    (net (code "6") (name "Net-(D193-DI)") (class "Default")
      (node (ref "D193") (pin "4-DIN") (pinfunction "DI_4-DIN") (pintype "input"))
      (node (ref "R12") (pin "1") (pinfunction "1_1") (pintype "passive"))
      (node (ref "R13") (pin "2") (pinfunction "2_2") (pintype "passive"))
    )
    (net (code "7") (name "Net-(D193-DO)") (class "Default")
      (node (ref "D193") (pin "2-DOUT") (pinfunction "DO_2-DOUT") (pintype "output"))
      (node (ref "D194") (pin "4-DIN") (pinfunction "DI_4-DIN") (pintype "input"))
    )
    (net (code "8") (name "Net-(D194-DO)") (class "Default")
      (node (ref "D194") (pin "2-DOUT") (pinfunction "DO_2-DOUT") (pintype "output"))
      (node (ref "D195") (pin "4-DIN") (pinfunction "DI_4-DIN") (pintype "input"))
    )
    (net (code "9") (name "Net-(D195-DO)") (class "Default")
      (node (ref "D195") (pin "2-DOUT") (pinfunction "DO_2-DOUT") (pintype "output"))
      (node (ref "D196") (pin "4-DIN") (pinfunction "DI_4-DIN") (pintype "input"))
    )
    (net (code "10") (name "Net-(D196-DO)") (class "Default")
      (node (ref "D196") (pin "2-DOUT") (pinfunction "DO_2-DOUT") (pintype "output"))
      (node (ref "D197") (pin "4-DIN") (pinfunction "DI_4-DIN") (pintype "input"))
    )
    (net (code "11") (name "Net-(D197-DO)") (class "Default")
      (node (ref "D197") (pin "2-DOUT") (pinfunction "DO_2-DOUT") (pintype "output"))
      (node (ref "D198") (pin "4-DIN") (pinfunction "DI_4-DIN") (pintype "input"))
    )
    (net (code "12") (name "Net-(D198-DO)") (class "Default")
      (node (ref "D198") (pin "2-DOUT") (pinfunction "DO_2-DOUT") (pintype "output"))
      (node (ref "D199") (pin "4-DIN") (pinfunction "DI_4-DIN") (pintype "input"))
    )
    (net (code "13") (name "Net-(D199-DO)") (class "Default")
      (node (ref "D199") (pin "2-DOUT") (pinfunction "DO_2-DOUT") (pintype "output"))
      (node (ref "D200") (pin "4-DIN") (pinfunction "DI_4-DIN") (pintype "input"))
    )
    (net (code "14") (name "Net-(D200-DO)") (class "Default")
      (node (ref "D200") (pin "2-DOUT") (pinfunction "DO_2-DOUT") (pintype "output"))
      (node (ref "D201") (pin "4-DIN") (pinfunction "DI_4-DIN") (pintype "input"))
    )
    (net (code "15") (name "Net-(D201-DO)") (class "Default")
      (node (ref "D201") (pin "2-DOUT") (pinfunction "DO_2-DOUT") (pintype "output"))
      (node (ref "D202") (pin "4-DIN") (pinfunction "DI_4-DIN") (pintype "input"))
    )
    (net (code "16") (name "Net-(D202-DO)") (class "Default")
      (node (ref "D202") (pin "2-DOUT") (pinfunction "DO_2-DOUT") (pintype "output"))
      (node (ref "D203") (pin "4-DIN") (pinfunction "DI_4-DIN") (pintype "input"))
    )
    (net (code "17") (name "Net-(D203-DO)") (class "Default")
      (node (ref "D203") (pin "2-DOUT") (pinfunction "DO_2-DOUT") (pintype "output"))
      (node (ref "D204") (pin "4-DIN") (pinfunction "DI_4-DIN") (pintype "input"))
    )
    (net (code "18") (name "Net-(D204-DO)") (class "Default")
      (node (ref "D204") (pin "2-DOUT") (pinfunction "DO_2-DOUT") (pintype "output"))
      (node (ref "D205") (pin "4-DIN") (pinfunction "DI_4-DIN") (pintype "input"))
    )
    (net (code "19") (name "Net-(D205-DO)") (class "Default")
      (node (ref "D205") (pin "2-DOUT") (pinfunction "DO_2-DOUT") (pintype "output"))
      (node (ref "D206") (pin "4-DIN") (pinfunction "DI_4-DIN") (pintype "input"))
    )
    (net (code "20") (name "Net-(D206-DO)") (class "Default")
      (node (ref "D206") (pin "2-DOUT") (pinfunction "DO_2-DOUT") (pintype "output"))
      (node (ref "D207") (pin "4-DIN") (pinfunction "DI_4-DIN") (pintype "input"))
    )
    (net (code "21") (name "Net-(D207-DO)") (class "Default")
      (node (ref "D207") (pin "2-DOUT") (pinfunction "DO_2-DOUT") (pintype "output"))
      (node (ref "D208") (pin "4-DIN") (pinfunction "DI_4-DIN") (pintype "input"))
    )
    (net (code "22") (name "Net-(D208-DO)") (class "Default")
      (node (ref "D208") (pin "2-DOUT") (pinfunction "DO_2-DOUT") (pintype "output"))
      (node (ref "D209") (pin "4-DIN") (pinfunction "DI_4-DIN") (pintype "input"))
    )
    (net (code "23") (name "Net-(D209-DO)") (class "Default")
      (node (ref "D209") (pin "2-DOUT") (pinfunction "DO_2-DOUT") (pintype "output"))
      (node (ref "D210") (pin "4-DIN") (pinfunction "DI_4-DIN") (pintype "input"))
    )
    (net (code "24") (name "Net-(D210-DO)") (class "Default")
      (node (ref "D210") (pin "2-DOUT") (pinfunction "DO_2-DOUT") (pintype "output"))
      (node (ref "D211") (pin "4-DIN") (pinfunction "DI_4-DIN") (pintype "input"))
    )
    (net (code "25") (name "Net-(D211-DO)") (class "Default")
      (node (ref "D211") (pin "2-DOUT") (pinfunction "DO_2-DOUT") (pintype "output"))
      (node (ref "D212") (pin "4-DIN") (pinfunction "DI_4-DIN") (pintype "input"))
    )
    (net (code "26") (name "Net-(D212-DO)") (class "Default")
      (node (ref "D212") (pin "2-DOUT") (pinfunction "DO_2-DOUT") (pintype "output"))
      (node (ref "D213") (pin "4-DIN") (pinfunction "DI_4-DIN") (pintype "input"))
    )
    (net (code "27") (name "Net-(D213-DO)") (class "Default")
      (node (ref "D213") (pin "2-DOUT") (pinfunction "DO_2-DOUT") (pintype "output"))
      (node (ref "D214") (pin "4-DIN") (pinfunction "DI_4-DIN") (pintype "input"))
    )
    (net (code "28") (name "Net-(D214-DO)") (class "Default")
      (node (ref "D214") (pin "2-DOUT") (pinfunction "DO_2-DOUT") (pintype "output"))
      (node (ref "D215") (pin "4-DIN") (pinfunction "DI_4-DIN") (pintype "input"))
    )
    (net (code "29") (name "Net-(D215-DO)") (class "Default")
      (node (ref "D215") (pin "2-DOUT") (pinfunction "DO_2-DOUT") (pintype "output"))
      (node (ref "D216") (pin "4-DIN") (pinfunction "DI_4-DIN") (pintype "input"))
    )
    (net (code "30") (name "Net-(D216-DO)") (class "Default")
      (node (ref "D216") (pin "2-DOUT") (pinfunction "DO_2-DOUT") (pintype "output"))
      (node (ref "R14") (pin "2") (pinfunction "2_2") (pintype "passive"))
    )
    (net (code "31") (name "Net-(D217-DI)") (class "Default")
      (node (ref "D217") (pin "4-DIN") (pinfunction "DI_4-DIN") (pintype "input"))
      (node (ref "R14") (pin "1") (pinfunction "1_1") (pintype "passive"))
    )
    (net (code "32") (name "Net-(D217-DO)") (class "Default")
      (node (ref "D217") (pin "2-DOUT") (pinfunction "DO_2-DOUT") (pintype "output"))
      (node (ref "D218") (pin "4-DIN") (pinfunction "DI_4-DIN") (pintype "input"))
    )
    (net (code "33") (name "Net-(D218-DO)") (class "Default")
      (node (ref "D218") (pin "2-DOUT") (pinfunction "DO_2-DOUT") (pintype "output"))
      (node (ref "D219") (pin "4-DIN") (pinfunction "DI_4-DIN") (pintype "input"))
    )
    (net (code "34") (name "Net-(D219-DO)") (class "Default")
      (node (ref "D219") (pin "2-DOUT") (pinfunction "DO_2-DOUT") (pintype "output"))
      (node (ref "D220") (pin "4-DIN") (pinfunction "DI_4-DIN") (pintype "input"))
    )
    (net (code "35") (name "Net-(D220-DO)") (class "Default")
      (node (ref "D220") (pin "2-DOUT") (pinfunction "DO_2-DOUT") (pintype "output"))
      (node (ref "D221") (pin "4-DIN") (pinfunction "DI_4-DIN") (pintype "input"))
    )
    (net (code "36") (name "Net-(D221-DO)") (class "Default")
      (node (ref "D221") (pin "2-DOUT") (pinfunction "DO_2-DOUT") (pintype "output"))
      (node (ref "D222") (pin "4-DIN") (pinfunction "DI_4-DIN") (pintype "input"))
    )
    (net (code "37") (name "Net-(D222-DO)") (class "Default")
      (node (ref "D222") (pin "2-DOUT") (pinfunction "DO_2-DOUT") (pintype "output"))
      (node (ref "D223") (pin "4-DIN") (pinfunction "DI_4-DIN") (pintype "input"))
    )
    (net (code "38") (name "Net-(D223-DO)") (class "Default")
      (node (ref "D223") (pin "2-DOUT") (pinfunction "DO_2-DOUT") (pintype "output"))
      (node (ref "D224") (pin "4-DIN") (pinfunction "DI_4-DIN") (pintype "input"))
    )
    (net (code "39") (name "Net-(D224-DO)") (class "Default")
      (node (ref "D224") (pin "2-DOUT") (pinfunction "DO_2-DOUT") (pintype "output"))
      (node (ref "D225") (pin "4-DIN") (pinfunction "DI_4-DIN") (pintype "input"))
    )
    (net (code "40") (name "Net-(D225-DO)") (class "Default")
      (node (ref "D225") (pin "2-DOUT") (pinfunction "DO_2-DOUT") (pintype "output"))
      (node (ref "D226") (pin "4-DIN") (pinfunction "DI_4-DIN") (pintype "input"))
    )
    (net (code "41") (name "Net-(D226-DO)") (class "Default")
      (node (ref "D226") (pin "2-DOUT") (pinfunction "DO_2-DOUT") (pintype "output"))
      (node (ref "D227") (pin "4-DIN") (pinfunction "DI_4-DIN") (pintype "input"))
    )
    (net (code "42") (name "Net-(D227-DO)") (class "Default")
      (node (ref "D227") (pin "2-DOUT") (pinfunction "DO_2-DOUT") (pintype "output"))
      (node (ref "D228") (pin "4-DIN") (pinfunction "DI_4-DIN") (pintype "input"))
    )
    (net (code "43") (name "Net-(D228-DO)") (class "Default")
      (node (ref "D228") (pin "2-DOUT") (pinfunction "DO_2-DOUT") (pintype "output"))
      (node (ref "D229") (pin "4-DIN") (pinfunction "DI_4-DIN") (pintype "input"))
    )
    (net (code "44") (name "Net-(D229-DO)") (class "Default")
      (node (ref "D229") (pin "2-DOUT") (pinfunction "DO_2-DOUT") (pintype "output"))
      (node (ref "D230") (pin "4-DIN") (pinfunction "DI_4-DIN") (pintype "input"))
    )
    (net (code "45") (name "Net-(D230-DO)") (class "Default")
      (node (ref "D230") (pin "2-DOUT") (pinfunction "DO_2-DOUT") (pintype "output"))
      (node (ref "D231") (pin "4-DIN") (pinfunction "DI_4-DIN") (pintype "input"))
    )
    (net (code "46") (name "Net-(D231-DO)") (class "Default")
      (node (ref "D231") (pin "2-DOUT") (pinfunction "DO_2-DOUT") (pintype "output"))
      (node (ref "D232") (pin "4-DIN") (pinfunction "DI_4-DIN") (pintype "input"))
    )
    (net (code "47") (name "Net-(D232-DO)") (class "Default")
      (node (ref "D232") (pin "2-DOUT") (pinfunction "DO_2-DOUT") (pintype "output"))
      (node (ref "D233") (pin "4-DIN") (pinfunction "DI_4-DIN") (pintype "input"))
    )
    (net (code "48") (name "Net-(D233-DO)") (class "Default")
      (node (ref "D233") (pin "2-DOUT") (pinfunction "DO_2-DOUT") (pintype "output"))
      (node (ref "D234") (pin "4-DIN") (pinfunction "DI_4-DIN") (pintype "input"))
    )
    (net (code "49") (name "Net-(D234-DO)") (class "Default")
      (node (ref "D234") (pin "2-DOUT") (pinfunction "DO_2-DOUT") (pintype "output"))
      (node (ref "D235") (pin "4-DIN") (pinfunction "DI_4-DIN") (pintype "input"))
    )
    (net (code "50") (name "Net-(D235-DO)") (class "Default")
      (node (ref "D235") (pin "2-DOUT") (pinfunction "DO_2-DOUT") (pintype "output"))
      (node (ref "D236") (pin "4-DIN") (pinfunction "DI_4-DIN") (pintype "input"))
    )
    (net (code "51") (name "Net-(D236-DO)") (class "Default")
      (node (ref "D236") (pin "2-DOUT") (pinfunction "DO_2-DOUT") (pintype "output"))
      (node (ref "D237") (pin "4-DIN") (pinfunction "DI_4-DIN") (pintype "input"))
    )
    (net (code "52") (name "Net-(D237-DO)") (class "Default")
      (node (ref "D237") (pin "2-DOUT") (pinfunction "DO_2-DOUT") (pintype "output"))
      (node (ref "D238") (pin "4-DIN") (pinfunction "DI_4-DIN") (pintype "input"))
    )
    (net (code "53") (name "Net-(D238-DO)") (class "Default")
      (node (ref "D238") (pin "2-DOUT") (pinfunction "DO_2-DOUT") (pintype "output"))
      (node (ref "D239") (pin "4-DIN") (pinfunction "DI_4-DIN") (pintype "input"))
    )
    (net (code "54") (name "Net-(D239-DO)") (class "Default")
      (node (ref "D239") (pin "2-DOUT") (pinfunction "DO_2-DOUT") (pintype "output"))
      (node (ref "D240") (pin "4-DIN") (pinfunction "DI_4-DIN") (pintype "input"))
    )
  )
)
